# untitled.net
KiCad netlist of a schematic drawn in EAGLE
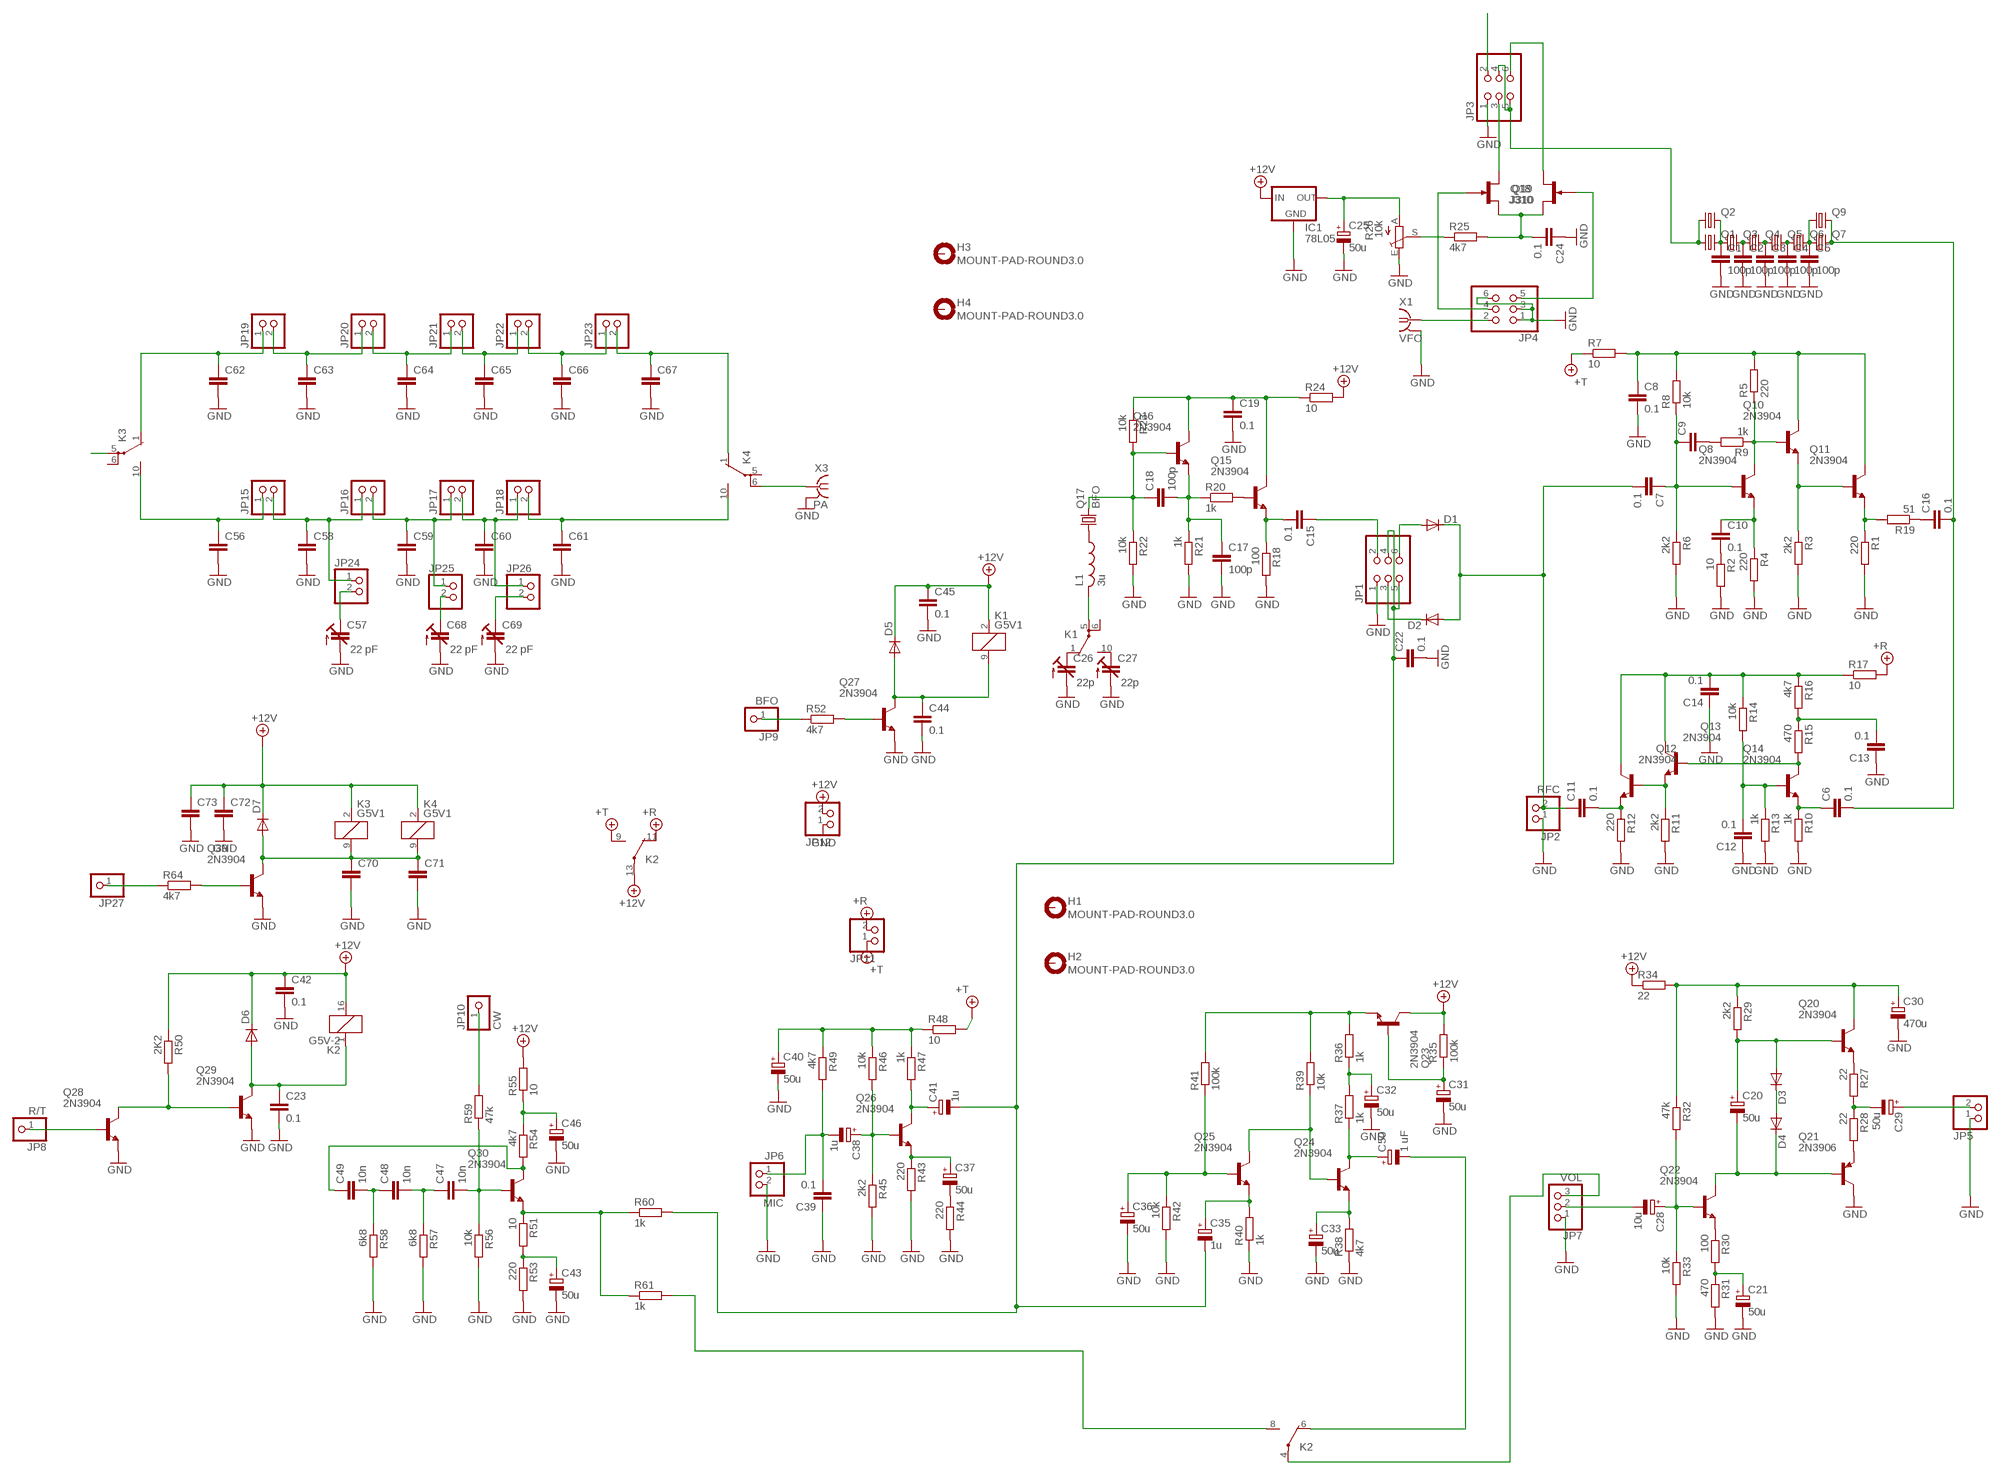
[diagram p0: schematic, sheet 1]

(export (version "E")
  (design (tool "Eeschema 10.0.6"))
  (components
    (comp (ref "C1")
      (value "100p")
      (footprint "eagle-import:C1206")
      (libsource (lib "eagle-import") (part "C-EUC1206"))
    )
    (comp (ref "C2")
      (value "100p")
      (footprint "eagle-import:C1206")
      (libsource (lib "eagle-import") (part "C-EUC1206"))
    )
    (comp (ref "C3")
      (value "100p")
      (footprint "eagle-import:C1206")
      (libsource (lib "eagle-import") (part "C-EUC1206"))
    )
    (comp (ref "C4")
      (value "100p")
      (footprint "eagle-import:C1206")
      (libsource (lib "eagle-import") (part "C-EUC1206"))
    )
    (comp (ref "C5")
      (value "100p")
      (footprint "eagle-import:C1206")
      (libsource (lib "eagle-import") (part "C-EUC1206"))
    )
    (comp (ref "C6")
      (value "0.1")
      (footprint "eagle-import:C050-024X044")
      (libsource (lib "eagle-import") (part "C-EU050-024X044"))
    )
    (comp (ref "C7")
      (value "0.1")
      (footprint "eagle-import:C050-024X044")
      (libsource (lib "eagle-import") (part "C-EU050-024X044"))
    )
    (comp (ref "C8")
      (value "0.1")
      (footprint "eagle-import:C050-024X044")
      (libsource (lib "eagle-import") (part "C-EU050-024X044"))
    )
    (comp (ref "C9")
      (value "C-EU050-024X044")
      (footprint "eagle-import:C050-024X044")
      (libsource (lib "eagle-import") (part "C-EU050-024X044"))
    )
    (comp (ref "C10")
      (value "0.1")
      (footprint "eagle-import:C050-024X044")
      (libsource (lib "eagle-import") (part "C-EU050-024X044"))
    )
    (comp (ref "C11")
      (value "0.1")
      (footprint "eagle-import:C050-024X044")
      (libsource (lib "eagle-import") (part "C-EU050-024X044"))
    )
    (comp (ref "C12")
      (value "0.1")
      (footprint "eagle-import:C050-024X044")
      (libsource (lib "eagle-import") (part "C-EU050-024X044"))
    )
    (comp (ref "C13")
      (value "0.1")
      (footprint "eagle-import:C050-024X044")
      (libsource (lib "eagle-import") (part "C-EU050-024X044"))
    )
    (comp (ref "C14")
      (value "0.1")
      (footprint "eagle-import:C050-024X044")
      (libsource (lib "eagle-import") (part "C-EU050-024X044"))
    )
    (comp (ref "C15")
      (value "0.1")
      (footprint "eagle-import:C050-024X044")
      (libsource (lib "eagle-import") (part "C-EU050-024X044"))
    )
    (comp (ref "C16")
      (value "0.1")
      (footprint "eagle-import:C050-024X044")
      (libsource (lib "eagle-import") (part "C-EU050-024X044"))
    )
    (comp (ref "C17")
      (value "100p")
      (footprint "eagle-import:C050-024X044")
      (libsource (lib "eagle-import") (part "C-EU050-024X044"))
    )
    (comp (ref "C18")
      (value "100p")
      (footprint "eagle-import:C050-024X044")
      (libsource (lib "eagle-import") (part "C-EU050-024X044"))
    )
    (comp (ref "C19")
      (value "0.1")
      (footprint "eagle-import:C050-024X044")
      (libsource (lib "eagle-import") (part "C-EU050-024X044"))
    )
    (comp (ref "C20")
      (value "50u")
      (footprint "eagle-import:E2,5-5")
      (libsource (lib "eagle-import") (part "CPOL-EUE2.5-5"))
    )
    (comp (ref "C21")
      (value "50u")
      (footprint "eagle-import:E2,5-5")
      (libsource (lib "eagle-import") (part "CPOL-EUE2.5-5"))
    )
    (comp (ref "C22")
      (value "0.1")
      (footprint "eagle-import:C050-024X044")
      (libsource (lib "eagle-import") (part "C-EU050-024X044"))
    )
    (comp (ref "C23")
      (value "0.1")
      (footprint "eagle-import:C050-024X044")
      (libsource (lib "eagle-import") (part "C-EU050-024X044"))
    )
    (comp (ref "C24")
      (value "0.1")
      (footprint "eagle-import:C050-024X044")
      (libsource (lib "eagle-import") (part "C-EU050-024X044"))
    )
    (comp (ref "C25")
      (value "50u")
      (footprint "eagle-import:E2,5-5")
      (libsource (lib "eagle-import") (part "CPOL-EUE2.5-5"))
    )
    (comp (ref "C26")
      (value "22p")
      (footprint "eagle-import:CTRIMTZ03")
      (libsource (lib "eagle-import") (part "C-TRIMMTZ03"))
    )
    (comp (ref "C27")
      (value "22p")
      (footprint "eagle-import:CTRIMTZ03")
      (libsource (lib "eagle-import") (part "C-TRIMMTZ03"))
    )
    (comp (ref "C28")
      (value "10u")
      (footprint "eagle-import:E2,5-5")
      (libsource (lib "eagle-import") (part "CPOL-EUE2.5-5"))
    )
    (comp (ref "C29")
      (value "50u")
      (footprint "eagle-import:E2,5-5")
      (libsource (lib "eagle-import") (part "CPOL-EUE2.5-5"))
    )
    (comp (ref "C30")
      (value "470u")
      (footprint "eagle-import:E2,5-5")
      (libsource (lib "eagle-import") (part "CPOL-EUE2.5-5"))
    )
    (comp (ref "C31")
      (value "50u")
      (footprint "eagle-import:E2,5-5")
      (libsource (lib "eagle-import") (part "CPOL-EUE2.5-5"))
    )
    (comp (ref "C32")
      (value "50u")
      (footprint "eagle-import:E2,5-5")
      (libsource (lib "eagle-import") (part "CPOL-EUE2.5-5"))
    )
    (comp (ref "C33")
      (value "50u")
      (footprint "eagle-import:E2,5-5")
      (libsource (lib "eagle-import") (part "CPOL-EUE2.5-5"))
    )
    (comp (ref "C35")
      (value "1u")
      (footprint "eagle-import:E2,5-5")
      (libsource (lib "eagle-import") (part "CPOL-EUE2.5-5"))
    )
    (comp (ref "C36")
      (value "50u")
      (footprint "eagle-import:E2,5-5")
      (libsource (lib "eagle-import") (part "CPOL-EUE2.5-5"))
    )
    (comp (ref "C37")
      (value "50u")
      (footprint "eagle-import:E2,5-5")
      (libsource (lib "eagle-import") (part "CPOL-EUE2.5-5"))
    )
    (comp (ref "C38")
      (value "1u")
      (footprint "eagle-import:E2,5-5")
      (libsource (lib "eagle-import") (part "CPOL-EUE2.5-5"))
    )
    (comp (ref "C39")
      (value "0.1")
      (footprint "eagle-import:C050-024X044")
      (libsource (lib "eagle-import") (part "C-EU050-024X044"))
    )
    (comp (ref "C40")
      (value "50u")
      (footprint "eagle-import:E2,5-5")
      (libsource (lib "eagle-import") (part "CPOL-EUE2.5-5"))
    )
    (comp (ref "C41")
      (value "1u")
      (footprint "eagle-import:E2,5-5")
      (libsource (lib "eagle-import") (part "CPOL-EUE2.5-5"))
    )
    (comp (ref "C42")
      (value "0.1")
      (footprint "eagle-import:C050-024X044")
      (libsource (lib "eagle-import") (part "C-EU050-024X044"))
    )
    (comp (ref "C43")
      (value "50u")
      (footprint "eagle-import:E2,5-5")
      (libsource (lib "eagle-import") (part "CPOL-EUE2.5-5"))
    )
    (comp (ref "C44")
      (value "0.1")
      (footprint "eagle-import:C050-024X044")
      (libsource (lib "eagle-import") (part "C-EU050-024X044"))
    )
    (comp (ref "C45")
      (value "0.1")
      (footprint "eagle-import:C050-024X044")
      (libsource (lib "eagle-import") (part "C-EU050-024X044"))
    )
    (comp (ref "C46")
      (value "50u")
      (footprint "eagle-import:E2,5-5")
      (libsource (lib "eagle-import") (part "CPOL-EUE2.5-5"))
    )
    (comp (ref "C47")
      (value "10n")
      (footprint "eagle-import:C050-024X044")
      (libsource (lib "eagle-import") (part "C-EU050-024X044"))
    )
    (comp (ref "C48")
      (value "10n")
      (footprint "eagle-import:C050-024X044")
      (libsource (lib "eagle-import") (part "C-EU050-024X044"))
    )
    (comp (ref "C49")
      (value "10n")
      (footprint "eagle-import:C050-024X044")
      (libsource (lib "eagle-import") (part "C-EU050-024X044"))
    )
    (comp (ref "C50")
      (value "1 uF")
      (footprint "eagle-import:E5-4")
      (libsource (lib "eagle-import") (part "CPOL-EUE5-4"))
    )
    (comp (ref "C56")
      (value "C-EU050-024X044")
      (footprint "eagle-import:C050-024X044")
      (libsource (lib "eagle-import") (part "C-EU050-024X044"))
    )
    (comp (ref "C57")
      (value "22 pF")
      (footprint "eagle-import:CTRIMTZ03")
      (libsource (lib "eagle-import") (part "C-TRIMMTZ03"))
    )
    (comp (ref "C58")
      (value "C-EU050-024X044")
      (footprint "eagle-import:C050-024X044")
      (libsource (lib "eagle-import") (part "C-EU050-024X044"))
    )
    (comp (ref "C59")
      (value "C-EU050-024X044")
      (footprint "eagle-import:C050-024X044")
      (libsource (lib "eagle-import") (part "C-EU050-024X044"))
    )
    (comp (ref "C60")
      (value "C-EU050-024X044")
      (footprint "eagle-import:C050-024X044")
      (libsource (lib "eagle-import") (part "C-EU050-024X044"))
    )
    (comp (ref "C61")
      (value "C-EU050-024X044")
      (footprint "eagle-import:C050-024X044")
      (libsource (lib "eagle-import") (part "C-EU050-024X044"))
    )
    (comp (ref "C62")
      (value "C-EU050-024X044")
      (footprint "eagle-import:C050-024X044")
      (libsource (lib "eagle-import") (part "C-EU050-024X044"))
    )
    (comp (ref "C63")
      (value "C-EU050-024X044")
      (footprint "eagle-import:C050-024X044")
      (libsource (lib "eagle-import") (part "C-EU050-024X044"))
    )
    (comp (ref "C64")
      (value "C-EU050-024X044")
      (footprint "eagle-import:C050-024X044")
      (libsource (lib "eagle-import") (part "C-EU050-024X044"))
    )
    (comp (ref "C65")
      (value "C-EU050-024X044")
      (footprint "eagle-import:C050-024X044")
      (libsource (lib "eagle-import") (part "C-EU050-024X044"))
    )
    (comp (ref "C66")
      (value "C-EU050-024X044")
      (footprint "eagle-import:C050-024X044")
      (libsource (lib "eagle-import") (part "C-EU050-024X044"))
    )
    (comp (ref "C67")
      (value "C-EU050-024X044")
      (footprint "eagle-import:C050-024X044")
      (libsource (lib "eagle-import") (part "C-EU050-024X044"))
    )
    (comp (ref "C68")
      (value "22 pF")
      (footprint "eagle-import:CTRIMTZ03")
      (libsource (lib "eagle-import") (part "C-TRIMMTZ03"))
    )
    (comp (ref "C69")
      (value "22 pF")
      (footprint "eagle-import:CTRIMTZ03")
      (libsource (lib "eagle-import") (part "C-TRIMMTZ03"))
    )
    (comp (ref "C70")
      (value "C-EU050-024X044")
      (footprint "eagle-import:C050-024X044")
      (libsource (lib "eagle-import") (part "C-EU050-024X044"))
    )
    (comp (ref "C71")
      (value "C-EU050-024X044")
      (footprint "eagle-import:C050-024X044")
      (libsource (lib "eagle-import") (part "C-EU050-024X044"))
    )
    (comp (ref "C72")
      (value "C-EU050-024X044")
      (footprint "eagle-import:C050-024X044")
      (libsource (lib "eagle-import") (part "C-EU050-024X044"))
    )
    (comp (ref "C73")
      (value "C-EU050-024X044")
      (footprint "eagle-import:C050-024X044")
      (libsource (lib "eagle-import") (part "C-EU050-024X044"))
    )
    (comp (ref "D1")
      (value "DIODE-D-5")
      (footprint "eagle-import:D-5")
      (libsource (lib "eagle-import") (part "DIODE-D-5"))
    )
    (comp (ref "D2")
      (value "DIODE-D-5")
      (footprint "eagle-import:D-5")
      (libsource (lib "eagle-import") (part "DIODE-D-5"))
    )
    (comp (ref "D3")
      (value "DIODE-D-5")
      (footprint "eagle-import:D-5")
      (libsource (lib "eagle-import") (part "DIODE-D-5"))
    )
    (comp (ref "D4")
      (value "DIODE-D-5")
      (footprint "eagle-import:D-5")
      (libsource (lib "eagle-import") (part "DIODE-D-5"))
    )
    (comp (ref "D5")
      (value "DIODE-D-5")
      (footprint "eagle-import:D-5")
      (libsource (lib "eagle-import") (part "DIODE-D-5"))
    )
    (comp (ref "D6")
      (value "DIODE-D-5")
      (footprint "eagle-import:D-5")
      (libsource (lib "eagle-import") (part "DIODE-D-5"))
    )
    (comp (ref "D7")
      (value "DIODE-D-5")
      (footprint "eagle-import:D-5")
      (libsource (lib "eagle-import") (part "DIODE-D-5"))
    )
    (comp (ref "H1")
      (value "MOUNT-PAD-ROUND3.0")
      (footprint "eagle-import:3,0-PAD")
      (libsource (lib "eagle-import") (part "MOUNT-PAD-ROUND3.0"))
    )
    (comp (ref "H2")
      (value "MOUNT-PAD-ROUND3.0")
      (footprint "eagle-import:3,0-PAD")
      (libsource (lib "eagle-import") (part "MOUNT-PAD-ROUND3.0"))
    )
    (comp (ref "H3")
      (value "MOUNT-PAD-ROUND3.0")
      (footprint "eagle-import:3,0-PAD")
      (libsource (lib "eagle-import") (part "MOUNT-PAD-ROUND3.0"))
    )
    (comp (ref "H4")
      (value "MOUNT-PAD-ROUND3.0")
      (footprint "eagle-import:3,0-PAD")
      (libsource (lib "eagle-import") (part "MOUNT-PAD-ROUND3.0"))
    )
    (comp (ref "IC1")
      (value "78L05")
      (footprint "eagle-import:78LXX")
      (libsource (lib "eagle-import") (part "78LXX"))
    )
    (comp (ref "JP1")
      (value "PINHD-2X3")
      (footprint "eagle-import:2X03")
      (libsource (lib "eagle-import") (part "PINHD-2X3"))
    )
    (comp (ref "JP2")
      (value "RFC")
      (footprint "eagle-import:1X02")
      (libsource (lib "eagle-import") (part "PINHD-1X2"))
    )
    (comp (ref "JP3")
      (value "PINHD-2X3")
      (footprint "eagle-import:2X03")
      (libsource (lib "eagle-import") (part "PINHD-2X3"))
    )
    (comp (ref "JP4")
      (value "PINHD-2X3")
      (footprint "eagle-import:2X03")
      (libsource (lib "eagle-import") (part "PINHD-2X3"))
    )
    (comp (ref "JP5")
      (value "PINHD-1X2")
      (footprint "eagle-import:1X02")
      (libsource (lib "eagle-import") (part "PINHD-1X2"))
    )
    (comp (ref "JP6")
      (value "MIC")
      (footprint "eagle-import:1X02")
      (libsource (lib "eagle-import") (part "PINHD-1X2"))
    )
    (comp (ref "JP7")
      (value "VOL")
      (footprint "eagle-import:1X03")
      (libsource (lib "eagle-import") (part "PINHD-1X3"))
    )
    (comp (ref "JP8")
      (value "R/T")
      (footprint "eagle-import:1X01")
      (libsource (lib "eagle-import") (part "PINHD-1X1"))
    )
    (comp (ref "JP9")
      (value "BFO")
      (footprint "eagle-import:1X01")
      (libsource (lib "eagle-import") (part "PINHD-1X1"))
    )
    (comp (ref "JP10")
      (value "CW")
      (footprint "eagle-import:1X01")
      (libsource (lib "eagle-import") (part "PINHD-1X1"))
    )
    (comp (ref "JP11")
      (value "PINHD-1X2")
      (footprint "eagle-import:1X02")
      (libsource (lib "eagle-import") (part "PINHD-1X2"))
    )
    (comp (ref "JP12")
      (value "PINHD-1X2")
      (footprint "eagle-import:1X02")
      (libsource (lib "eagle-import") (part "PINHD-1X2"))
    )
    (comp (ref "JP15")
      (value "PINHD-1X2")
      (footprint "eagle-import:1X02")
      (libsource (lib "eagle-import") (part "PINHD-1X2"))
    )
    (comp (ref "JP16")
      (value "PINHD-1X2")
      (footprint "eagle-import:1X02")
      (libsource (lib "eagle-import") (part "PINHD-1X2"))
    )
    (comp (ref "JP17")
      (value "PINHD-1X2")
      (footprint "eagle-import:1X02")
      (libsource (lib "eagle-import") (part "PINHD-1X2"))
    )
    (comp (ref "JP18")
      (value "PINHD-1X2")
      (footprint "eagle-import:1X02")
      (libsource (lib "eagle-import") (part "PINHD-1X2"))
    )
    (comp (ref "JP19")
      (value "PINHD-1X2")
      (footprint "eagle-import:1X02")
      (libsource (lib "eagle-import") (part "PINHD-1X2"))
    )
    (comp (ref "JP20")
      (value "PINHD-1X2")
      (footprint "eagle-import:1X02")
      (libsource (lib "eagle-import") (part "PINHD-1X2"))
    )
    (comp (ref "JP21")
      (value "PINHD-1X2")
      (footprint "eagle-import:1X02")
      (libsource (lib "eagle-import") (part "PINHD-1X2"))
    )
    (comp (ref "JP22")
      (value "PINHD-1X2")
      (footprint "eagle-import:1X02")
      (libsource (lib "eagle-import") (part "PINHD-1X2"))
    )
    (comp (ref "JP23")
      (value "PINHD-1X2")
      (footprint "eagle-import:1X02")
      (libsource (lib "eagle-import") (part "PINHD-1X2"))
    )
    (comp (ref "JP24")
      (value "PINHD-1X2")
      (footprint "eagle-import:1X02")
      (libsource (lib "eagle-import") (part "PINHD-1X2"))
    )
    (comp (ref "JP25")
      (value "PINHD-1X2")
      (footprint "eagle-import:1X02")
      (libsource (lib "eagle-import") (part "PINHD-1X2"))
    )
    (comp (ref "JP26")
      (value "PINHD-1X2")
      (footprint "eagle-import:1X02")
      (libsource (lib "eagle-import") (part "PINHD-1X2"))
    )
    (comp (ref "JP27")
      (value "PINHD-1X1")
      (footprint "eagle-import:1X01")
      (libsource (lib "eagle-import") (part "PINHD-1X1"))
    )
    (comp (ref "K1")
      (value "G5V1")
      (footprint "eagle-import:G5V1")
      (fields (field (name "MPN") "G5V-1-DC24"))
      (libsource (lib "eagle-import") (part "G5V1"))
    )
    (comp (ref "K2")
      (value "G5V-2")
      (footprint "eagle-import:G5V-2")
      (fields (field (name "MPN") "G5V-2 5DC"))
      (libsource (lib "eagle-import") (part "G5V-2"))
    )
    (comp (ref "K3")
      (value "G5V1")
      (footprint "eagle-import:G5V1")
      (fields (field (name "MPN") "G5V-1-DC24"))
      (libsource (lib "eagle-import") (part "G5V1"))
    )
    (comp (ref "K4")
      (value "G5V1")
      (footprint "eagle-import:G5V1")
      (fields (field (name "MPN") "G5V-1-DC24"))
      (libsource (lib "eagle-import") (part "G5V1"))
    )
    (comp (ref "L1")
      (value "3u")
      (footprint "eagle-import:0207_2V")
      (libsource (lib "eagle-import") (part "L-US0207/2V"))
    )
    (comp (ref "Q1")
      (value "CRYSTALHC49S")
      (footprint "eagle-import:HC49_S")
      (libsource (lib "eagle-import") (part "CRYSTALHC49S"))
    )
    (comp (ref "Q2")
      (value "CRYSTALHC49S")
      (footprint "eagle-import:HC49_S")
      (libsource (lib "eagle-import") (part "CRYSTALHC49S"))
    )
    (comp (ref "Q3")
      (value "CRYSTALHC49S")
      (footprint "eagle-import:HC49_S")
      (libsource (lib "eagle-import") (part "CRYSTALHC49S"))
    )
    (comp (ref "Q4")
      (value "CRYSTALHC49S")
      (footprint "eagle-import:HC49_S")
      (libsource (lib "eagle-import") (part "CRYSTALHC49S"))
    )
    (comp (ref "Q5")
      (value "CRYSTALHC49S")
      (footprint "eagle-import:HC49_S")
      (libsource (lib "eagle-import") (part "CRYSTALHC49S"))
    )
    (comp (ref "Q6")
      (value "CRYSTALHC49S")
      (footprint "eagle-import:HC49_S")
      (libsource (lib "eagle-import") (part "CRYSTALHC49S"))
    )
    (comp (ref "Q7")
      (value "CRYSTALHC49S")
      (footprint "eagle-import:HC49_S")
      (libsource (lib "eagle-import") (part "CRYSTALHC49S"))
    )
    (comp (ref "Q8")
      (value "2N3904")
      (footprint "eagle-import:TO92")
      (libsource (lib "eagle-import") (part "2N3904"))
    )
    (comp (ref "Q9")
      (value "CRYSTALHC49S")
      (footprint "eagle-import:HC49_S")
      (libsource (lib "eagle-import") (part "CRYSTALHC49S"))
    )
    (comp (ref "Q10")
      (value "2N3904")
      (footprint "eagle-import:TO92")
      (libsource (lib "eagle-import") (part "2N3904"))
    )
    (comp (ref "Q11")
      (value "2N3904")
      (footprint "eagle-import:TO92")
      (libsource (lib "eagle-import") (part "2N3904"))
    )
    (comp (ref "Q12")
      (value "2N3904")
      (footprint "eagle-import:TO92")
      (libsource (lib "eagle-import") (part "2N3904"))
    )
    (comp (ref "Q13")
      (value "2N3904")
      (footprint "eagle-import:TO92")
      (libsource (lib "eagle-import") (part "2N3904"))
    )
    (comp (ref "Q14")
      (value "2N3904")
      (footprint "eagle-import:TO92")
      (libsource (lib "eagle-import") (part "2N3904"))
    )
    (comp (ref "Q15")
      (value "2N3904")
      (footprint "eagle-import:TO92")
      (libsource (lib "eagle-import") (part "2N3904"))
    )
    (comp (ref "Q16")
      (value "2N3904")
      (footprint "eagle-import:TO92")
      (libsource (lib "eagle-import") (part "2N3904"))
    )
    (comp (ref "Q17")
      (value "BFO")
      (footprint "eagle-import:HC49_S")
      (fields (field (name "OC_FARNELL") "1667008") (field (name "OC_NEWARK") "unknown"))
      (libsource (lib "eagle-import") (part "CRYSTALHC49S"))
    )
    (comp (ref "Q18")
      (value "J310")
      (footprint "eagle-import:TO92R")
      (libsource (lib "eagle-import") (part "J310"))
    )
    (comp (ref "Q19")
      (value "J310")
      (footprint "eagle-import:TO92R")
      (libsource (lib "eagle-import") (part "J310"))
    )
    (comp (ref "Q20")
      (value "2N3904")
      (footprint "eagle-import:TO92")
      (libsource (lib "eagle-import") (part "2N3904"))
    )
    (comp (ref "Q21")
      (value "2N3906")
      (footprint "eagle-import:TO92")
      (libsource (lib "eagle-import") (part "2N3906"))
    )
    (comp (ref "Q22")
      (value "2N3904")
      (footprint "eagle-import:TO92")
      (libsource (lib "eagle-import") (part "2N3904"))
    )
    (comp (ref "Q23")
      (value "2N3904")
      (footprint "eagle-import:TO92")
      (libsource (lib "eagle-import") (part "2N3904"))
    )
    (comp (ref "Q24")
      (value "2N3904")
      (footprint "eagle-import:TO92")
      (libsource (lib "eagle-import") (part "2N3904"))
    )
    (comp (ref "Q25")
      (value "2N3904")
      (footprint "eagle-import:TO92")
      (libsource (lib "eagle-import") (part "2N3904"))
    )
    (comp (ref "Q26")
      (value "2N3904")
      (footprint "eagle-import:TO92")
      (libsource (lib "eagle-import") (part "2N3904"))
    )
    (comp (ref "Q27")
      (value "2N3904")
      (footprint "eagle-import:TO92")
      (libsource (lib "eagle-import") (part "2N3904"))
    )
    (comp (ref "Q28")
      (value "2N3904")
      (footprint "eagle-import:TO92")
      (libsource (lib "eagle-import") (part "2N3904"))
    )
    (comp (ref "Q29")
      (value "2N3904")
      (footprint "eagle-import:TO92")
      (libsource (lib "eagle-import") (part "2N3904"))
    )
    (comp (ref "Q30")
      (value "2N3904")
      (footprint "eagle-import:TO92")
      (libsource (lib "eagle-import") (part "2N3904"))
    )
    (comp (ref "Q39")
      (value "2N3904")
      (footprint "eagle-import:TO92")
      (libsource (lib "eagle-import") (part "2N3904"))
    )
    (comp (ref "R1")
      (value "220")
      (footprint "eagle-import:0204_5")
      (libsource (lib "eagle-import") (part "R-EU_0204/5"))
    )
    (comp (ref "R2")
      (value "10")
      (footprint "eagle-import:0204_5")
      (libsource (lib "eagle-import") (part "R-EU_0204/5"))
    )
    (comp (ref "R3")
      (value "2k2")
      (footprint "eagle-import:0204_5")
      (libsource (lib "eagle-import") (part "R-EU_0204/5"))
    )
    (comp (ref "R4")
      (value "220")
      (footprint "eagle-import:0204_5")
      (libsource (lib "eagle-import") (part "R-EU_0204/5"))
    )
    (comp (ref "R5")
      (value "220")
      (footprint "eagle-import:0204_5")
      (libsource (lib "eagle-import") (part "R-EU_0204/5"))
    )
    (comp (ref "R6")
      (value "2k2")
      (footprint "eagle-import:0204_5")
      (libsource (lib "eagle-import") (part "R-EU_0204/5"))
    )
    (comp (ref "R7")
      (value "10")
      (footprint "eagle-import:0204_5")
      (libsource (lib "eagle-import") (part "R-EU_0204/5"))
    )
    (comp (ref "R8")
      (value "10k")
      (footprint "eagle-import:0204_5")
      (libsource (lib "eagle-import") (part "R-EU_0204/5"))
    )
    (comp (ref "R9")
      (value "1k")
      (footprint "eagle-import:0204_5")
      (libsource (lib "eagle-import") (part "R-EU_0204/5"))
    )
    (comp (ref "R10")
      (value "1k")
      (footprint "eagle-import:0204_5")
      (libsource (lib "eagle-import") (part "R-EU_0204/5"))
    )
    (comp (ref "R11")
      (value "2k2")
      (footprint "eagle-import:0204_5")
      (libsource (lib "eagle-import") (part "R-EU_0204/5"))
    )
    (comp (ref "R12")
      (value "220")
      (footprint "eagle-import:0204_5")
      (libsource (lib "eagle-import") (part "R-EU_0204/5"))
    )
    (comp (ref "R13")
      (value "1k")
      (footprint "eagle-import:0204_5")
      (libsource (lib "eagle-import") (part "R-EU_0204/5"))
    )
    (comp (ref "R14")
      (value "10k")
      (footprint "eagle-import:0204_5")
      (libsource (lib "eagle-import") (part "R-EU_0204/5"))
    )
    (comp (ref "R15")
      (value "470")
      (footprint "eagle-import:0204_5")
      (libsource (lib "eagle-import") (part "R-EU_0204/5"))
    )
    (comp (ref "R16")
      (value "4k7")
      (footprint "eagle-import:0204_5")
      (libsource (lib "eagle-import") (part "R-EU_0204/5"))
    )
    (comp (ref "R17")
      (value "10")
      (footprint "eagle-import:0204_5")
      (libsource (lib "eagle-import") (part "R-EU_0204/5"))
    )
    (comp (ref "R18")
      (value "100")
      (footprint "eagle-import:0204_5")
      (libsource (lib "eagle-import") (part "R-EU_0204/5"))
    )
    (comp (ref "R19")
      (value "51")
      (footprint "eagle-import:0204_5")
      (libsource (lib "eagle-import") (part "R-EU_0204/5"))
    )
    (comp (ref "R20")
      (value "1k")
      (footprint "eagle-import:0204_5")
      (libsource (lib "eagle-import") (part "R-EU_0204/5"))
    )
    (comp (ref "R21")
      (value "1k")
      (footprint "eagle-import:0204_5")
      (libsource (lib "eagle-import") (part "R-EU_0204/5"))
    )
    (comp (ref "R22")
      (value "10k")
      (footprint "eagle-import:0204_5")
      (libsource (lib "eagle-import") (part "R-EU_0204/5"))
    )
    (comp (ref "R23")
      (value "10k")
      (footprint "eagle-import:0204_5")
      (libsource (lib "eagle-import") (part "R-EU_0204/5"))
    )
    (comp (ref "R24")
      (value "10")
      (footprint "eagle-import:0204_5")
      (libsource (lib "eagle-import") (part "R-EU_0204/5"))
    )
    (comp (ref "R25")
      (value "4k7")
      (footprint "eagle-import:0204_5")
      (libsource (lib "eagle-import") (part "R-EU_0204/5"))
    )
    (comp (ref "R26")
      (value "10k")
      (footprint "eagle-import:CA6V")
      (libsource (lib "eagle-import") (part "TRIM_EU-CA6V"))
    )
    (comp (ref "R27")
      (value "22")
      (footprint "eagle-import:0204_5")
      (libsource (lib "eagle-import") (part "R-EU_0204/5"))
    )
    (comp (ref "R28")
      (value "22")
      (footprint "eagle-import:0204_5")
      (libsource (lib "eagle-import") (part "R-EU_0204/5"))
    )
    (comp (ref "R29")
      (value "2k2")
      (footprint "eagle-import:0204_5")
      (libsource (lib "eagle-import") (part "R-EU_0204/5"))
    )
    (comp (ref "R30")
      (value "100")
      (footprint "eagle-import:0204_5")
      (libsource (lib "eagle-import") (part "R-EU_0204/5"))
    )
    (comp (ref "R31")
      (value "470")
      (footprint "eagle-import:0204_5")
      (libsource (lib "eagle-import") (part "R-EU_0204/5"))
    )
    (comp (ref "R32")
      (value "47k")
      (footprint "eagle-import:0204_5")
      (libsource (lib "eagle-import") (part "R-EU_0204/5"))
    )
    (comp (ref "R33")
      (value "10k")
      (footprint "eagle-import:0204_5")
      (libsource (lib "eagle-import") (part "R-EU_0204/5"))
    )
    (comp (ref "R34")
      (value "22")
      (footprint "eagle-import:0204_5")
      (libsource (lib "eagle-import") (part "R-EU_0204/5"))
    )
    (comp (ref "R35")
      (value "100k")
      (footprint "eagle-import:0204_5")
      (libsource (lib "eagle-import") (part "R-EU_0204/5"))
    )
    (comp (ref "R36")
      (value "1k")
      (footprint "eagle-import:0204_5")
      (libsource (lib "eagle-import") (part "R-EU_0204/5"))
    )
    (comp (ref "R37")
      (value "1k")
      (footprint "eagle-import:0204_5")
      (libsource (lib "eagle-import") (part "R-EU_0204/5"))
    )
    (comp (ref "R38")
      (value "4k7")
      (footprint "eagle-import:0204_5")
      (libsource (lib "eagle-import") (part "R-EU_0204/5"))
    )
    (comp (ref "R39")
      (value "10k")
      (footprint "eagle-import:0204_5")
      (libsource (lib "eagle-import") (part "R-EU_0204/5"))
    )
    (comp (ref "R40")
      (value "1k")
      (footprint "eagle-import:0204_5")
      (libsource (lib "eagle-import") (part "R-EU_0204/5"))
    )
    (comp (ref "R41")
      (value "100k")
      (footprint "eagle-import:0204_5")
      (libsource (lib "eagle-import") (part "R-EU_0204/5"))
    )
    (comp (ref "R42")
      (value "10k")
      (footprint "eagle-import:0204_5")
      (libsource (lib "eagle-import") (part "R-EU_0204/5"))
    )
    (comp (ref "R43")
      (value "220")
      (footprint "eagle-import:0204_5")
      (libsource (lib "eagle-import") (part "R-EU_0204/5"))
    )
    (comp (ref "R44")
      (value "220")
      (footprint "eagle-import:0204_5")
      (libsource (lib "eagle-import") (part "R-EU_0204/5"))
    )
    (comp (ref "R45")
      (value "2k2")
      (footprint "eagle-import:0204_5")
      (libsource (lib "eagle-import") (part "R-EU_0204/5"))
    )
    (comp (ref "R46")
      (value "10k")
      (footprint "eagle-import:0204_5")
      (libsource (lib "eagle-import") (part "R-EU_0204/5"))
    )
    (comp (ref "R47")
      (value "1k")
      (footprint "eagle-import:0204_5")
      (libsource (lib "eagle-import") (part "R-EU_0204/5"))
    )
    (comp (ref "R48")
      (value "10")
      (footprint "eagle-import:0204_5")
      (libsource (lib "eagle-import") (part "R-EU_0204/5"))
    )
    (comp (ref "R49")
      (value "4k7")
      (footprint "eagle-import:0204_5")
      (libsource (lib "eagle-import") (part "R-EU_0204/5"))
    )
    (comp (ref "R50")
      (value "2K2")
      (footprint "eagle-import:0204_5")
      (libsource (lib "eagle-import") (part "R-EU_0204/5"))
    )
    (comp (ref "R51")
      (value "10")
      (footprint "eagle-import:0204_5")
      (libsource (lib "eagle-import") (part "R-EU_0204/5"))
    )
    (comp (ref "R52")
      (value "4k7")
      (footprint "eagle-import:0204_5")
      (libsource (lib "eagle-import") (part "R-EU_0204/5"))
    )
    (comp (ref "R53")
      (value "220")
      (footprint "eagle-import:0204_5")
      (libsource (lib "eagle-import") (part "R-EU_0204/5"))
    )
    (comp (ref "R54")
      (value "4k7")
      (footprint "eagle-import:0204_5")
      (libsource (lib "eagle-import") (part "R-EU_0204/5"))
    )
    (comp (ref "R55")
      (value "10")
      (footprint "eagle-import:0204_5")
      (libsource (lib "eagle-import") (part "R-EU_0204/5"))
    )
    (comp (ref "R56")
      (value "10k")
      (footprint "eagle-import:0204_5")
      (libsource (lib "eagle-import") (part "R-EU_0204/5"))
    )
    (comp (ref "R57")
      (value "6k8")
      (footprint "eagle-import:0204_5")
      (libsource (lib "eagle-import") (part "R-EU_0204/5"))
    )
    (comp (ref "R58")
      (value "6k8")
      (footprint "eagle-import:0204_5")
      (libsource (lib "eagle-import") (part "R-EU_0204/5"))
    )
    (comp (ref "R59")
      (value "47k")
      (footprint "eagle-import:0204_5")
      (libsource (lib "eagle-import") (part "R-EU_0204/5"))
    )
    (comp (ref "R60")
      (value "1k")
      (footprint "eagle-import:0204_5")
      (libsource (lib "eagle-import") (part "R-EU_0204/5"))
    )
    (comp (ref "R61")
      (value "1k")
      (footprint "eagle-import:0204_5")
      (libsource (lib "eagle-import") (part "R-EU_0204/5"))
    )
    (comp (ref "R64")
      (value "4k7")
      (footprint "eagle-import:0204_5")
      (libsource (lib "eagle-import") (part "R-EU_0204/5"))
    )
    (comp (ref "X1")
      (value "VFO")
      (footprint "eagle-import:BU-SMA-V")
      (libsource (lib "eagle-import") (part "BU-SMA-V"))
    )
    (comp (ref "X3")
      (value "PA")
      (footprint "eagle-import:BU-SMA-V")
      (fields (field (name "OC_FARNELL") "unknown") (field (name "OC_NEWARK") "unknown"))
      (libsource (lib "eagle-import") (part "BU-SMA-V"))
    )
  )
  (nets
    (net (code "1") (name "+12V") (class "Default")
      (node (ref "C42") (pin "1") (pinfunction "1_1") (pintype "passive"))
      (node (ref "C45") (pin "1") (pinfunction "1_1") (pintype "passive"))
      (node (ref "C72") (pin "1") (pinfunction "1_1") (pintype "passive"))
      (node (ref "C73") (pin "1") (pinfunction "1_1") (pintype "passive"))
      (node (ref "D5") (pin "C") (pinfunction "C_C") (pintype "passive"))
      (node (ref "D6") (pin "C") (pinfunction "C_C") (pintype "passive"))
      (node (ref "D7") (pin "C") (pinfunction "C_C") (pintype "passive"))
      (node (ref "IC1") (pin "IN") (pinfunction "IN_IN") (pintype "input"))
      (node (ref "JP12") (pin "2") (pinfunction "2_2") (pintype "passive"))
      (node (ref "K1") (pin "2") (pinfunction "1_2") (pintype "passive"))
      (node (ref "K2") (pin "13") (pinfunction "P_13") (pintype "passive"))
      (node (ref "K2") (pin "16") (pinfunction "2_16") (pintype "passive"))
      (node (ref "K3") (pin "2") (pinfunction "1_2") (pintype "passive"))
      (node (ref "K4") (pin "2") (pinfunction "1_2") (pintype "passive"))
      (node (ref "Q23") (pin "1") (pinfunction "C_1") (pintype "passive"))
      (node (ref "R24") (pin "2") (pinfunction "2_2") (pintype "passive"))
      (node (ref "R34") (pin "1") (pinfunction "1_1") (pintype "passive"))
      (node (ref "R35") (pin "2") (pinfunction "2_2") (pintype "passive"))
      (node (ref "R50") (pin "1") (pinfunction "1_1") (pintype "passive"))
      (node (ref "R55") (pin "2") (pinfunction "2_2") (pintype "passive"))
    )
    (net (code "2") (name "+R") (class "Default")
      (node (ref "JP11") (pin "2") (pinfunction "2_2") (pintype "passive"))
      (node (ref "K2") (pin "11") (pinfunction "O_11") (pintype "passive"))
      (node (ref "R17") (pin "2") (pinfunction "2_2") (pintype "passive"))
    )
    (net (code "3") (name "+T") (class "Default")
      (node (ref "JP11") (pin "1") (pinfunction "1_1") (pintype "passive"))
      (node (ref "K2") (pin "9") (pinfunction "S_9") (pintype "passive"))
      (node (ref "R48") (pin "2") (pinfunction "2_2") (pintype "passive"))
      (node (ref "R7") (pin "1") (pinfunction "1_1") (pintype "passive"))
    )
    (net (code "4") (name "/N$116") (class "Default")
      (node (ref "JP3") (pin "2") (pinfunction "2_2") (pintype "passive"))
      (node (ref "K3") (pin "5") (pinfunction "P_5") (pintype "passive"))
    )
    (net (code "5") (name "GND") (class "Default")
      (node (ref "C1") (pin "2") (pinfunction "2_2") (pintype "passive"))
      (node (ref "C12") (pin "1") (pinfunction "1_1") (pintype "passive"))
      (node (ref "C13") (pin "1") (pinfunction "1_1") (pintype "passive"))
      (node (ref "C14") (pin "1") (pinfunction "1_1") (pintype "passive"))
      (node (ref "C17") (pin "2") (pinfunction "2_2") (pintype "passive"))
      (node (ref "C19") (pin "2") (pinfunction "2_2") (pintype "passive"))
      (node (ref "C2") (pin "2") (pinfunction "2_2") (pintype "passive"))
      (node (ref "C21") (pin "-") (pinfunction "-_-") (pintype "passive"))
      (node (ref "C22") (pin "2") (pinfunction "2_2") (pintype "passive"))
      (node (ref "C23") (pin "2") (pinfunction "2_2") (pintype "passive"))
      (node (ref "C24") (pin "1") (pinfunction "1_1") (pintype "passive"))
      (node (ref "C25") (pin "-") (pinfunction "-_-") (pintype "passive"))
      (node (ref "C26") (pin "2") (pinfunction "A_2") (pintype "passive"))
      (node (ref "C27") (pin "2") (pinfunction "A_2") (pintype "passive"))
      (node (ref "C3") (pin "2") (pinfunction "2_2") (pintype "passive"))
      (node (ref "C30") (pin "-") (pinfunction "-_-") (pintype "passive"))
      (node (ref "C31") (pin "-") (pinfunction "-_-") (pintype "passive"))
      (node (ref "C32") (pin "-") (pinfunction "-_-") (pintype "passive"))
      (node (ref "C33") (pin "-") (pinfunction "-_-") (pintype "passive"))
      (node (ref "C36") (pin "-") (pinfunction "-_-") (pintype "passive"))
      (node (ref "C39") (pin "1") (pinfunction "1_1") (pintype "passive"))
      (node (ref "C4") (pin "2") (pinfunction "2_2") (pintype "passive"))
      (node (ref "C40") (pin "-") (pinfunction "-_-") (pintype "passive"))
      (node (ref "C42") (pin "2") (pinfunction "2_2") (pintype "passive"))
      (node (ref "C43") (pin "-") (pinfunction "-_-") (pintype "passive"))
      (node (ref "C44") (pin "2") (pinfunction "2_2") (pintype "passive"))
      (node (ref "C45") (pin "2") (pinfunction "2_2") (pintype "passive"))
      (node (ref "C46") (pin "-") (pinfunction "-_-") (pintype "passive"))
      (node (ref "C5") (pin "2") (pinfunction "2_2") (pintype "passive"))
      (node (ref "C56") (pin "2") (pinfunction "2_2") (pintype "passive"))
      (node (ref "C57") (pin "2") (pinfunction "A_2") (pintype "passive"))
      (node (ref "C58") (pin "2") (pinfunction "2_2") (pintype "passive"))
      (node (ref "C59") (pin "2") (pinfunction "2_2") (pintype "passive"))
      (node (ref "C60") (pin "2") (pinfunction "2_2") (pintype "passive"))
      (node (ref "C61") (pin "2") (pinfunction "2_2") (pintype "passive"))
      (node (ref "C62") (pin "2") (pinfunction "2_2") (pintype "passive"))
      (node (ref "C63") (pin "2") (pinfunction "2_2") (pintype "passive"))
      (node (ref "C64") (pin "2") (pinfunction "2_2") (pintype "passive"))
      (node (ref "C65") (pin "2") (pinfunction "2_2") (pintype "passive"))
      (node (ref "C66") (pin "2") (pinfunction "2_2") (pintype "passive"))
      (node (ref "C67") (pin "2") (pinfunction "2_2") (pintype "passive"))
      (node (ref "C68") (pin "2") (pinfunction "A_2") (pintype "passive"))
      (node (ref "C69") (pin "2") (pinfunction "A_2") (pintype "passive"))
      (node (ref "C70") (pin "2") (pinfunction "2_2") (pintype "passive"))
      (node (ref "C71") (pin "2") (pinfunction "2_2") (pintype "passive"))
      (node (ref "C72") (pin "2") (pinfunction "2_2") (pintype "passive"))
      (node (ref "C73") (pin "2") (pinfunction "2_2") (pintype "passive"))
      (node (ref "C8") (pin "2") (pinfunction "2_2") (pintype "passive"))
      (node (ref "IC1") (pin "GND") (pinfunction "GND_GND") (pintype "input"))
      (node (ref "JP1") (pin "1") (pinfunction "1_1") (pintype "passive"))
      (node (ref "JP12") (pin "1") (pinfunction "1_1") (pintype "passive"))
      (node (ref "JP2") (pin "1") (pinfunction "1_1") (pintype "passive"))
      (node (ref "JP3") (pin "1") (pinfunction "1_1") (pintype "passive"))
      (node (ref "JP4") (pin "1") (pinfunction "1_1") (pintype "passive"))
      (node (ref "JP4") (pin "3") (pinfunction "3_3") (pintype "passive"))
      (node (ref "JP4") (pin "6") (pinfunction "6_6") (pintype "passive"))
      (node (ref "JP5") (pin "1") (pinfunction "1_1") (pintype "passive"))
      (node (ref "JP6") (pin "2") (pinfunction "2_2") (pintype "passive"))
      (node (ref "JP7") (pin "1") (pinfunction "1_1") (pintype "passive"))
      (node (ref "Q21") (pin "1") (pinfunction "C_1") (pintype "passive"))
      (node (ref "Q27") (pin "3") (pinfunction "E_3") (pintype "passive"))
      (node (ref "Q28") (pin "3") (pinfunction "E_3") (pintype "passive"))
      (node (ref "Q29") (pin "3") (pinfunction "E_3") (pintype "passive"))
      (node (ref "Q39") (pin "3") (pinfunction "E_3") (pintype "passive"))
      (node (ref "R1") (pin "2") (pinfunction "2_2") (pintype "passive"))
      (node (ref "R10") (pin "2") (pinfunction "2_2") (pintype "passive"))
      (node (ref "R11") (pin "2") (pinfunction "2_2") (pintype "passive"))
      (node (ref "R12") (pin "2") (pinfunction "2_2") (pintype "passive"))
      (node (ref "R13") (pin "2") (pinfunction "2_2") (pintype "passive"))
      (node (ref "R18") (pin "2") (pinfunction "2_2") (pintype "passive"))
      (node (ref "R2") (pin "2") (pinfunction "2_2") (pintype "passive"))
      (node (ref "R21") (pin "2") (pinfunction "2_2") (pintype "passive"))
      (node (ref "R22") (pin "2") (pinfunction "2_2") (pintype "passive"))
      (node (ref "R26") (pin "E") (pinfunction "E_E") (pintype "passive"))
      (node (ref "R3") (pin "2") (pinfunction "2_2") (pintype "passive"))
      (node (ref "R31") (pin "2") (pinfunction "2_2") (pintype "passive"))
      (node (ref "R33") (pin "2") (pinfunction "2_2") (pintype "passive"))
      (node (ref "R38") (pin "1") (pinfunction "1_1") (pintype "passive"))
      (node (ref "R4") (pin "2") (pinfunction "2_2") (pintype "passive"))
      (node (ref "R40") (pin "1") (pinfunction "1_1") (pintype "passive"))
      (node (ref "R42") (pin "2") (pinfunction "2_2") (pintype "passive"))
      (node (ref "R43") (pin "2") (pinfunction "2_2") (pintype "passive"))
      (node (ref "R44") (pin "2") (pinfunction "2_2") (pintype "passive"))
      (node (ref "R45") (pin "2") (pinfunction "2_2") (pintype "passive"))
      (node (ref "R53") (pin "2") (pinfunction "2_2") (pintype "passive"))
      (node (ref "R56") (pin "2") (pinfunction "2_2") (pintype "passive"))
      (node (ref "R57") (pin "2") (pinfunction "2_2") (pintype "passive"))
      (node (ref "R58") (pin "2") (pinfunction "2_2") (pintype "passive"))
      (node (ref "R6") (pin "2") (pinfunction "2_2") (pintype "passive"))
      (node (ref "X1") (pin "2") (pinfunction "GND_2") (pintype "power_in"))
      (node (ref "X3") (pin "2") (pinfunction "GND_2") (pintype "power_in"))
    )
    (net (code "6") (name "Net-(C1-Pad1)") (class "Default")
      (node (ref "C1") (pin "1") (pinfunction "1_1") (pintype "passive"))
      (node (ref "Q1") (pin "2") (pinfunction "2_2") (pintype "passive"))
      (node (ref "Q2") (pin "2") (pinfunction "2_2") (pintype "passive"))
      (node (ref "Q3") (pin "1") (pinfunction "1_1") (pintype "passive"))
    )
    (net (code "7") (name "Net-(C2-Pad1)") (class "Default")
      (node (ref "C2") (pin "1") (pinfunction "1_1") (pintype "passive"))
      (node (ref "Q3") (pin "2") (pinfunction "2_2") (pintype "passive"))
      (node (ref "Q4") (pin "1") (pinfunction "1_1") (pintype "passive"))
    )
    (net (code "8") (name "Net-(C3-Pad1)") (class "Default")
      (node (ref "C3") (pin "1") (pinfunction "1_1") (pintype "passive"))
      (node (ref "Q4") (pin "2") (pinfunction "2_2") (pintype "passive"))
      (node (ref "Q5") (pin "1") (pinfunction "1_1") (pintype "passive"))
    )
    (net (code "9") (name "Net-(C4-Pad1)") (class "Default")
      (node (ref "C4") (pin "1") (pinfunction "1_1") (pintype "passive"))
      (node (ref "Q5") (pin "2") (pinfunction "2_2") (pintype "passive"))
      (node (ref "Q6") (pin "1") (pinfunction "1_1") (pintype "passive"))
    )
    (net (code "10") (name "Net-(C5-Pad1)") (class "Default")
      (node (ref "C5") (pin "1") (pinfunction "1_1") (pintype "passive"))
      (node (ref "Q6") (pin "2") (pinfunction "2_2") (pintype "passive"))
      (node (ref "Q7") (pin "1") (pinfunction "1_1") (pintype "passive"))
      (node (ref "Q9") (pin "1") (pinfunction "1_1") (pintype "passive"))
    )
    (net (code "11") (name "Net-(C9-Pad2)") (class "Default")
      (node (ref "C9") (pin "2") (pinfunction "2_2") (pintype "passive"))
      (node (ref "R9") (pin "2") (pinfunction "2_2") (pintype "passive"))
    )
    (net (code "12") (name "Net-(C10-Pad2)") (class "Default")
      (node (ref "C10") (pin "2") (pinfunction "2_2") (pintype "passive"))
      (node (ref "R2") (pin "1") (pinfunction "1_1") (pintype "passive"))
    )
    (net (code "13") (name "Net-(C11-Pad1)") (class "Default")
      (node (ref "C11") (pin "1") (pinfunction "1_1") (pintype "passive"))
      (node (ref "C7") (pin "2") (pinfunction "2_2") (pintype "passive"))
      (node (ref "D1") (pin "C") (pinfunction "C_C") (pintype "passive"))
      (node (ref "D2") (pin "A") (pinfunction "A_A") (pintype "passive"))
      (node (ref "JP2") (pin "2") (pinfunction "2_2") (pintype "passive"))
    )
    (net (code "14") (name "Net-(C13-Pad2)") (class "Default")
      (node (ref "C13") (pin "2") (pinfunction "2_2") (pintype "passive"))
      (node (ref "R15") (pin "1") (pinfunction "1_1") (pintype "passive"))
      (node (ref "R16") (pin "2") (pinfunction "2_2") (pintype "passive"))
    )
    (net (code "15") (name "Net-(C15-Pad1)") (class "Default")
      (node (ref "C15") (pin "1") (pinfunction "1_1") (pintype "passive"))
      (node (ref "JP1") (pin "2") (pinfunction "2_2") (pintype "passive"))
    )
    (net (code "16") (name "Net-(C16-Pad1)") (class "Default")
      (node (ref "C16") (pin "1") (pinfunction "1_1") (pintype "passive"))
      (node (ref "R19") (pin "1") (pinfunction "1_1") (pintype "passive"))
    )
    (net (code "17") (name "Net-(C16-Pad2)") (class "Default")
      (node (ref "C16") (pin "2") (pinfunction "2_2") (pintype "passive"))
      (node (ref "C6") (pin "2") (pinfunction "2_2") (pintype "passive"))
      (node (ref "Q7") (pin "2") (pinfunction "2_2") (pintype "passive"))
      (node (ref "Q9") (pin "2") (pinfunction "2_2") (pintype "passive"))
    )
    (net (code "18") (name "Net-(C21-Pad+)") (class "Default")
      (node (ref "C21") (pin "+") (pinfunction "+_+") (pintype "passive"))
      (node (ref "R30") (pin "2") (pinfunction "2_2") (pintype "passive"))
      (node (ref "R31") (pin "1") (pinfunction "1_1") (pintype "passive"))
    )
    (net (code "19") (name "Net-(C22-Pad1)") (class "Default")
      (node (ref "C22") (pin "1") (pinfunction "1_1") (pintype "passive"))
      (node (ref "C35") (pin "-") (pinfunction "-_-") (pintype "passive"))
      (node (ref "C41") (pin "-") (pinfunction "-_-") (pintype "passive"))
      (node (ref "JP1") (pin "4") (pinfunction "4_4") (pintype "passive"))
      (node (ref "JP1") (pin "5") (pinfunction "5_5") (pintype "passive"))
      (node (ref "R60") (pin "2") (pinfunction "2_2") (pintype "passive"))
    )
    (net (code "20") (name "Net-(C24-Pad2)") (class "Default")
      (node (ref "C24") (pin "2") (pinfunction "2_2") (pintype "passive"))
      (node (ref "Q18") (pin "S") (pinfunction "S_S") (pintype "passive"))
      (node (ref "Q19") (pin "S") (pinfunction "S_S") (pintype "passive"))
      (node (ref "R25") (pin "2") (pinfunction "2_2") (pintype "passive"))
    )
    (net (code "21") (name "Net-(C25-Pad+)") (class "Default")
      (node (ref "C25") (pin "+") (pinfunction "+_+") (pintype "passive"))
      (node (ref "IC1") (pin "OUT") (pinfunction "OUT_OUT") (pintype "passive"))
      (node (ref "R26") (pin "A") (pinfunction "A_A") (pintype "passive"))
    )
    (net (code "22") (name "Net-(C26-E)") (class "Default")
      (node (ref "C26") (pin "1") (pinfunction "E_1") (pintype "passive"))
      (node (ref "K1") (pin "1") (pinfunction "O_1") (pintype "passive"))
    )
    (net (code "23") (name "Net-(C27-E)") (class "Default")
      (node (ref "C27") (pin "1") (pinfunction "E_1") (pintype "passive"))
      (node (ref "K1") (pin "10") (pinfunction "S_10") (pintype "passive"))
    )
    (net (code "24") (name "Net-(C28-Pad-)") (class "Default")
      (node (ref "C28") (pin "-") (pinfunction "-_-") (pintype "passive"))
      (node (ref "JP7") (pin "2") (pinfunction "2_2") (pintype "passive"))
    )
    (net (code "25") (name "Net-(C29-Pad+)") (class "Default")
      (node (ref "C29") (pin "+") (pinfunction "+_+") (pintype "passive"))
      (node (ref "JP5") (pin "2") (pinfunction "2_2") (pintype "passive"))
    )
    (net (code "26") (name "Net-(C29-Pad-)") (class "Default")
      (node (ref "C29") (pin "-") (pinfunction "-_-") (pintype "passive"))
      (node (ref "R27") (pin "2") (pinfunction "2_2") (pintype "passive"))
      (node (ref "R28") (pin "1") (pinfunction "1_1") (pintype "passive"))
    )
    (net (code "27") (name "Net-(C32-Pad+)") (class "Default")
      (node (ref "C32") (pin "+") (pinfunction "+_+") (pintype "passive"))
      (node (ref "R36") (pin "1") (pinfunction "1_1") (pintype "passive"))
      (node (ref "R37") (pin "2") (pinfunction "2_2") (pintype "passive"))
    )
    (net (code "28") (name "Net-(C37-Pad-)") (class "Default")
      (node (ref "C37") (pin "-") (pinfunction "-_-") (pintype "passive"))
      (node (ref "R44") (pin "1") (pinfunction "1_1") (pintype "passive"))
    )
    (net (code "29") (name "Net-(C38-Pad-)") (class "Default")
      (node (ref "C38") (pin "-") (pinfunction "-_-") (pintype "passive"))
      (node (ref "C39") (pin "2") (pinfunction "2_2") (pintype "passive"))
      (node (ref "JP6") (pin "1") (pinfunction "1_1") (pintype "passive"))
      (node (ref "R49") (pin "2") (pinfunction "2_2") (pintype "passive"))
    )
    (net (code "30") (name "Net-(C40-Pad+)") (class "Default")
      (node (ref "C40") (pin "+") (pinfunction "+_+") (pintype "passive"))
      (node (ref "R46") (pin "1") (pinfunction "1_1") (pintype "passive"))
      (node (ref "R47") (pin "1") (pinfunction "1_1") (pintype "passive"))
      (node (ref "R48") (pin "1") (pinfunction "1_1") (pintype "passive"))
      (node (ref "R49") (pin "1") (pinfunction "1_1") (pintype "passive"))
    )
    (net (code "31") (name "Net-(C43-Pad+)") (class "Default")
      (node (ref "C43") (pin "+") (pinfunction "+_+") (pintype "passive"))
      (node (ref "R51") (pin "2") (pinfunction "2_2") (pintype "passive"))
      (node (ref "R53") (pin "1") (pinfunction "1_1") (pintype "passive"))
    )
    (net (code "32") (name "Net-(C46-Pad+)") (class "Default")
      (node (ref "C46") (pin "+") (pinfunction "+_+") (pintype "passive"))
      (node (ref "R54") (pin "1") (pinfunction "1_1") (pintype "passive"))
      (node (ref "R55") (pin "1") (pinfunction "1_1") (pintype "passive"))
    )
    (net (code "33") (name "Net-(C47-Pad1)") (class "Default")
      (node (ref "C47") (pin "1") (pinfunction "1_1") (pintype "passive"))
      (node (ref "C48") (pin "2") (pinfunction "2_2") (pintype "passive"))
      (node (ref "R57") (pin "1") (pinfunction "1_1") (pintype "passive"))
    )
    (net (code "34") (name "Net-(C48-Pad1)") (class "Default")
      (node (ref "C48") (pin "1") (pinfunction "1_1") (pintype "passive"))
      (node (ref "C49") (pin "2") (pinfunction "2_2") (pintype "passive"))
      (node (ref "R58") (pin "1") (pinfunction "1_1") (pintype "passive"))
    )
    (net (code "35") (name "Net-(C57-E)") (class "Default")
      (node (ref "C57") (pin "1") (pinfunction "E_1") (pintype "passive"))
      (node (ref "JP24") (pin "2") (pinfunction "2_2") (pintype "passive"))
    )
    (net (code "36") (name "Net-(C58-Pad1)") (class "Default")
      (node (ref "C58") (pin "1") (pinfunction "1_1") (pintype "passive"))
      (node (ref "JP15") (pin "2") (pinfunction "2_2") (pintype "passive"))
      (node (ref "JP16") (pin "1") (pinfunction "1_1") (pintype "passive"))
      (node (ref "JP24") (pin "1") (pinfunction "1_1") (pintype "passive"))
    )
    (net (code "37") (name "Net-(C59-Pad1)") (class "Default")
      (node (ref "C59") (pin "1") (pinfunction "1_1") (pintype "passive"))
      (node (ref "JP16") (pin "2") (pinfunction "2_2") (pintype "passive"))
      (node (ref "JP17") (pin "1") (pinfunction "1_1") (pintype "passive"))
      (node (ref "JP25") (pin "1") (pinfunction "1_1") (pintype "passive"))
    )
    (net (code "38") (name "Net-(C60-Pad1)") (class "Default")
      (node (ref "C60") (pin "1") (pinfunction "1_1") (pintype "passive"))
      (node (ref "JP17") (pin "2") (pinfunction "2_2") (pintype "passive"))
      (node (ref "JP18") (pin "1") (pinfunction "1_1") (pintype "passive"))
      (node (ref "JP26") (pin "1") (pinfunction "1_1") (pintype "passive"))
    )
    (net (code "39") (name "Net-(C63-Pad1)") (class "Default")
      (node (ref "C63") (pin "1") (pinfunction "1_1") (pintype "passive"))
      (node (ref "JP19") (pin "2") (pinfunction "2_2") (pintype "passive"))
      (node (ref "JP20") (pin "1") (pinfunction "1_1") (pintype "passive"))
    )
    (net (code "40") (name "Net-(C64-Pad1)") (class "Default")
      (node (ref "C64") (pin "1") (pinfunction "1_1") (pintype "passive"))
      (node (ref "JP20") (pin "2") (pinfunction "2_2") (pintype "passive"))
      (node (ref "JP21") (pin "1") (pinfunction "1_1") (pintype "passive"))
    )
    (net (code "41") (name "Net-(C65-Pad1)") (class "Default")
      (node (ref "C65") (pin "1") (pinfunction "1_1") (pintype "passive"))
      (node (ref "JP21") (pin "2") (pinfunction "2_2") (pintype "passive"))
      (node (ref "JP22") (pin "1") (pinfunction "1_1") (pintype "passive"))
    )
    (net (code "42") (name "Net-(C66-Pad1)") (class "Default")
      (node (ref "C66") (pin "1") (pinfunction "1_1") (pintype "passive"))
      (node (ref "JP22") (pin "2") (pinfunction "2_2") (pintype "passive"))
      (node (ref "JP23") (pin "1") (pinfunction "1_1") (pintype "passive"))
    )
    (net (code "43") (name "Net-(C68-E)") (class "Default")
      (node (ref "C68") (pin "1") (pinfunction "E_1") (pintype "passive"))
      (node (ref "JP25") (pin "2") (pinfunction "2_2") (pintype "passive"))
    )
    (net (code "44") (name "Net-(C69-E)") (class "Default")
      (node (ref "C69") (pin "1") (pinfunction "E_1") (pintype "passive"))
      (node (ref "JP26") (pin "2") (pinfunction "2_2") (pintype "passive"))
    )
    (net (code "45") (name "Net-(D1-PadA)") (class "Default")
      (node (ref "D1") (pin "A") (pinfunction "A_A") (pintype "passive"))
      (node (ref "JP1") (pin "6") (pinfunction "6_6") (pintype "passive"))
    )
    (net (code "46") (name "Net-(D2-PadC)") (class "Default")
      (node (ref "D2") (pin "C") (pinfunction "C_C") (pintype "passive"))
      (node (ref "JP1") (pin "3") (pinfunction "3_3") (pintype "passive"))
    )
    (net (code "47") (name "Net-(D3-PadC)") (class "Default")
      (node (ref "D3") (pin "C") (pinfunction "C_C") (pintype "passive"))
      (node (ref "D4") (pin "A") (pinfunction "A_A") (pintype "passive"))
    )
    (net (code "48") (name "Net-(JP3-Pad3)") (class "Default")
      (node (ref "JP3") (pin "3") (pinfunction "3_3") (pintype "passive"))
      (node (ref "Q18") (pin "D") (pinfunction "D_D") (pintype "passive"))
    )
    (net (code "49") (name "Net-(JP3-Pad4)") (class "Default")
      (node (ref "JP3") (pin "4") (pinfunction "4_4") (pintype "passive"))
      (node (ref "JP3") (pin "5") (pinfunction "5_5") (pintype "passive"))
      (node (ref "Q1") (pin "1") (pinfunction "1_1") (pintype "passive"))
      (node (ref "Q2") (pin "1") (pinfunction "1_1") (pintype "passive"))
    )
    (net (code "50") (name "Net-(JP3-Pad6)") (class "Default")
      (node (ref "JP3") (pin "6") (pinfunction "6_6") (pintype "passive"))
      (node (ref "Q19") (pin "D") (pinfunction "D_D") (pintype "passive"))
    )
    (net (code "51") (name "Net-(JP4-Pad2)") (class "Default")
      (node (ref "JP4") (pin "2") (pinfunction "2_2") (pintype "passive"))
      (node (ref "X1") (pin "1") (pinfunction "1_1") (pintype "passive"))
    )
    (net (code "52") (name "Net-(JP4-Pad4)") (class "Default")
      (node (ref "JP4") (pin "4") (pinfunction "4_4") (pintype "passive"))
      (node (ref "Q18") (pin "G") (pinfunction "G_G") (pintype "passive"))
    )
    (net (code "53") (name "Net-(JP4-Pad5)") (class "Default")
      (node (ref "JP4") (pin "5") (pinfunction "5_5") (pintype "passive"))
      (node (ref "Q19") (pin "G") (pinfunction "G_G") (pintype "passive"))
    )
    (net (code "54") (name "Net-(JP9-Pad1)") (class "Default")
      (node (ref "JP9") (pin "1") (pinfunction "1_1") (pintype "passive"))
      (node (ref "R52") (pin "1") (pinfunction "1_1") (pintype "passive"))
    )
    (net (code "55") (name "Net-(JP10-Pad1)") (class "Default")
      (node (ref "JP10") (pin "1") (pinfunction "1_1") (pintype "passive"))
      (node (ref "R59") (pin "2") (pinfunction "2_2") (pintype "passive"))
    )
    (net (code "56") (name "Net-(JP27-Pad1)") (class "Default")
      (node (ref "JP27") (pin "1") (pinfunction "1_1") (pintype "passive"))
      (node (ref "R64") (pin "1") (pinfunction "1_1") (pintype "passive"))
    )
    (net (code "57") (name "Net-(K1A-2)") (class "Default")
      (node (ref "C44") (pin "1") (pinfunction "1_1") (pintype "passive"))
      (node (ref "D5") (pin "A") (pinfunction "A_A") (pintype "passive"))
      (node (ref "K1") (pin "9") (pinfunction "2_9") (pintype "passive"))
      (node (ref "Q27") (pin "1") (pinfunction "C_1") (pintype "passive"))
    )
    (net (code "58") (name "Net-(K1B-P-Pad5)") (class "Default")
      (node (ref "K1") (pin "5") (pinfunction "P_5") (pintype "passive"))
      (node (ref "L1") (pin "2") (pinfunction "2_2") (pintype "passive"))
    )
    (net (code "59") (name "Net-(K2A-O)") (class "Default")
      (node (ref "C50") (pin "-") (pinfunction "-_-") (pintype "passive"))
      (node (ref "K2") (pin "6") (pinfunction "O_6") (pintype "passive"))
    )
    (net (code "60") (name "Net-(K2A-P)") (class "Default")
      (node (ref "JP7") (pin "3") (pinfunction "3_3") (pintype "passive"))
      (node (ref "K2") (pin "4") (pinfunction "P_4") (pintype "passive"))
    )
    (net (code "61") (name "Net-(K2A-S)") (class "Default")
      (node (ref "K2") (pin "8") (pinfunction "S_8") (pintype "passive"))
      (node (ref "R61") (pin "2") (pinfunction "2_2") (pintype "passive"))
    )
    (net (code "62") (name "Net-(K3A-2)") (class "Default")
      (node (ref "C70") (pin "1") (pinfunction "1_1") (pintype "passive"))
      (node (ref "C71") (pin "1") (pinfunction "1_1") (pintype "passive"))
      (node (ref "D7") (pin "A") (pinfunction "A_A") (pintype "passive"))
      (node (ref "K3") (pin "9") (pinfunction "2_9") (pintype "passive"))
      (node (ref "K4") (pin "9") (pinfunction "2_9") (pintype "passive"))
      (node (ref "Q39") (pin "1") (pinfunction "C_1") (pintype "passive"))
    )
    (net (code "63") (name "Net-(K3B-O)") (class "Default")
      (node (ref "C62") (pin "1") (pinfunction "1_1") (pintype "passive"))
      (node (ref "JP19") (pin "1") (pinfunction "1_1") (pintype "passive"))
      (node (ref "K3") (pin "1") (pinfunction "O_1") (pintype "passive"))
    )
    (net (code "64") (name "Net-(K3B-S)") (class "Default")
      (node (ref "C56") (pin "1") (pinfunction "1_1") (pintype "passive"))
      (node (ref "JP15") (pin "1") (pinfunction "1_1") (pintype "passive"))
      (node (ref "K3") (pin "10") (pinfunction "S_10") (pintype "passive"))
    )
    (net (code "65") (name "Net-(K4B-O)") (class "Default")
      (node (ref "C67") (pin "1") (pinfunction "1_1") (pintype "passive"))
      (node (ref "JP23") (pin "2") (pinfunction "2_2") (pintype "passive"))
      (node (ref "K4") (pin "1") (pinfunction "O_1") (pintype "passive"))
    )
    (net (code "66") (name "Net-(K4B-P-Pad6)") (class "Default")
      (node (ref "K4") (pin "6") (pinfunction "P_6") (pintype "passive"))
      (node (ref "X3") (pin "1") (pinfunction "1_1") (pintype "passive"))
    )
    (net (code "67") (name "Net-(K4B-S)") (class "Default")
      (node (ref "C61") (pin "1") (pinfunction "1_1") (pintype "passive"))
      (node (ref "JP18") (pin "2") (pinfunction "2_2") (pintype "passive"))
      (node (ref "K4") (pin "10") (pinfunction "S_10") (pintype "passive"))
    )
    (net (code "68") (name "Net-(L1-Pad1)") (class "Default")
      (node (ref "L1") (pin "1") (pinfunction "1_1") (pintype "passive"))
      (node (ref "Q17") (pin "1") (pinfunction "1_1") (pintype "passive"))
    )
    (net (code "69") (name "Net-(Q8-B)") (class "Default")
      (node (ref "C7") (pin "1") (pinfunction "1_1") (pintype "passive"))
      (node (ref "C9") (pin "1") (pinfunction "1_1") (pintype "passive"))
      (node (ref "Q8") (pin "2") (pinfunction "B_2") (pintype "passive"))
      (node (ref "R6") (pin "1") (pinfunction "1_1") (pintype "passive"))
      (node (ref "R8") (pin "1") (pinfunction "1_1") (pintype "passive"))
    )
    (net (code "70") (name "Net-(Q8-E)") (class "Default")
      (node (ref "C10") (pin "1") (pinfunction "1_1") (pintype "passive"))
      (node (ref "Q8") (pin "3") (pinfunction "E_3") (pintype "passive"))
      (node (ref "R4") (pin "1") (pinfunction "1_1") (pintype "passive"))
    )
    (net (code "71") (name "Net-(Q10-B)") (class "Default")
      (node (ref "Q10") (pin "2") (pinfunction "B_2") (pintype "passive"))
      (node (ref "Q8") (pin "1") (pinfunction "C_1") (pintype "passive"))
      (node (ref "R5") (pin "1") (pinfunction "1_1") (pintype "passive"))
      (node (ref "R9") (pin "1") (pinfunction "1_1") (pintype "passive"))
    )
    (net (code "72") (name "Net-(Q10-C)") (class "Default")
      (node (ref "C8") (pin "1") (pinfunction "1_1") (pintype "passive"))
      (node (ref "Q10") (pin "1") (pinfunction "C_1") (pintype "passive"))
      (node (ref "Q11") (pin "1") (pinfunction "C_1") (pintype "passive"))
      (node (ref "R5") (pin "2") (pinfunction "2_2") (pintype "passive"))
      (node (ref "R7") (pin "2") (pinfunction "2_2") (pintype "passive"))
      (node (ref "R8") (pin "2") (pinfunction "2_2") (pintype "passive"))
    )
    (net (code "73") (name "Net-(Q10-E)") (class "Default")
      (node (ref "Q10") (pin "3") (pinfunction "E_3") (pintype "passive"))
      (node (ref "Q11") (pin "2") (pinfunction "B_2") (pintype "passive"))
      (node (ref "R3") (pin "1") (pinfunction "1_1") (pintype "passive"))
    )
    (net (code "74") (name "Net-(Q11-E)") (class "Default")
      (node (ref "Q11") (pin "3") (pinfunction "E_3") (pintype "passive"))
      (node (ref "R1") (pin "1") (pinfunction "1_1") (pintype "passive"))
      (node (ref "R19") (pin "2") (pinfunction "2_2") (pintype "passive"))
    )
    (net (code "75") (name "Net-(Q12-B)") (class "Default")
      (node (ref "Q12") (pin "2") (pinfunction "B_2") (pintype "passive"))
      (node (ref "Q13") (pin "3") (pinfunction "E_3") (pintype "passive"))
      (node (ref "R11") (pin "1") (pinfunction "1_1") (pintype "passive"))
    )
    (net (code "76") (name "Net-(Q12-C)") (class "Default")
      (node (ref "C14") (pin "2") (pinfunction "2_2") (pintype "passive"))
      (node (ref "Q12") (pin "1") (pinfunction "C_1") (pintype "passive"))
      (node (ref "Q13") (pin "1") (pinfunction "C_1") (pintype "passive"))
      (node (ref "R14") (pin "1") (pinfunction "1_1") (pintype "passive"))
      (node (ref "R16") (pin "1") (pinfunction "1_1") (pintype "passive"))
      (node (ref "R17") (pin "1") (pinfunction "1_1") (pintype "passive"))
    )
    (net (code "77") (name "Net-(Q12-E)") (class "Default")
      (node (ref "C11") (pin "2") (pinfunction "2_2") (pintype "passive"))
      (node (ref "Q12") (pin "3") (pinfunction "E_3") (pintype "passive"))
      (node (ref "R12") (pin "1") (pinfunction "1_1") (pintype "passive"))
    )
    (net (code "78") (name "Net-(Q13-B)") (class "Default")
      (node (ref "Q13") (pin "2") (pinfunction "B_2") (pintype "passive"))
      (node (ref "Q14") (pin "1") (pinfunction "C_1") (pintype "passive"))
      (node (ref "R15") (pin "2") (pinfunction "2_2") (pintype "passive"))
    )
    (net (code "79") (name "Net-(Q14-B)") (class "Default")
      (node (ref "C12") (pin "2") (pinfunction "2_2") (pintype "passive"))
      (node (ref "Q14") (pin "2") (pinfunction "B_2") (pintype "passive"))
      (node (ref "R13") (pin "1") (pinfunction "1_1") (pintype "passive"))
      (node (ref "R14") (pin "2") (pinfunction "2_2") (pintype "passive"))
    )
    (net (code "80") (name "Net-(Q14-E)") (class "Default")
      (node (ref "C6") (pin "1") (pinfunction "1_1") (pintype "passive"))
      (node (ref "Q14") (pin "3") (pinfunction "E_3") (pintype "passive"))
      (node (ref "R10") (pin "1") (pinfunction "1_1") (pintype "passive"))
    )
    (net (code "81") (name "Net-(Q15-B)") (class "Default")
      (node (ref "Q15") (pin "2") (pinfunction "B_2") (pintype "passive"))
      (node (ref "R20") (pin "2") (pinfunction "2_2") (pintype "passive"))
    )
    (net (code "82") (name "Net-(Q15-C)") (class "Default")
      (node (ref "C19") (pin "1") (pinfunction "1_1") (pintype "passive"))
      (node (ref "Q15") (pin "1") (pinfunction "C_1") (pintype "passive"))
      (node (ref "Q16") (pin "1") (pinfunction "C_1") (pintype "passive"))
      (node (ref "R23") (pin "1") (pinfunction "1_1") (pintype "passive"))
      (node (ref "R24") (pin "1") (pinfunction "1_1") (pintype "passive"))
    )
    (net (code "83") (name "Net-(Q15-E)") (class "Default")
      (node (ref "C15") (pin "2") (pinfunction "2_2") (pintype "passive"))
      (node (ref "Q15") (pin "3") (pinfunction "E_3") (pintype "passive"))
      (node (ref "R18") (pin "1") (pinfunction "1_1") (pintype "passive"))
    )
    (net (code "84") (name "Net-(Q16-B)") (class "Default")
      (node (ref "C18") (pin "1") (pinfunction "1_1") (pintype "passive"))
      (node (ref "Q16") (pin "2") (pinfunction "B_2") (pintype "passive"))
      (node (ref "Q17") (pin "2") (pinfunction "2_2") (pintype "passive"))
      (node (ref "R22") (pin "1") (pinfunction "1_1") (pintype "passive"))
      (node (ref "R23") (pin "2") (pinfunction "2_2") (pintype "passive"))
    )
    (net (code "85") (name "Net-(Q16-E)") (class "Default")
      (node (ref "C17") (pin "1") (pinfunction "1_1") (pintype "passive"))
      (node (ref "C18") (pin "2") (pinfunction "2_2") (pintype "passive"))
      (node (ref "Q16") (pin "3") (pinfunction "E_3") (pintype "passive"))
      (node (ref "R20") (pin "1") (pinfunction "1_1") (pintype "passive"))
      (node (ref "R21") (pin "1") (pinfunction "1_1") (pintype "passive"))
    )
    (net (code "86") (name "Net-(Q20-B)") (class "Default")
      (node (ref "C20") (pin "+") (pinfunction "+_+") (pintype "passive"))
      (node (ref "D3") (pin "A") (pinfunction "A_A") (pintype "passive"))
      (node (ref "Q20") (pin "2") (pinfunction "B_2") (pintype "passive"))
      (node (ref "R29") (pin "2") (pinfunction "2_2") (pintype "passive"))
    )
    (net (code "87") (name "Net-(Q20-C)") (class "Default")
      (node (ref "C30") (pin "+") (pinfunction "+_+") (pintype "passive"))
      (node (ref "Q20") (pin "1") (pinfunction "C_1") (pintype "passive"))
      (node (ref "R29") (pin "1") (pinfunction "1_1") (pintype "passive"))
      (node (ref "R32") (pin "1") (pinfunction "1_1") (pintype "passive"))
      (node (ref "R34") (pin "2") (pinfunction "2_2") (pintype "passive"))
    )
    (net (code "88") (name "Net-(Q20-E)") (class "Default")
      (node (ref "Q20") (pin "3") (pinfunction "E_3") (pintype "passive"))
      (node (ref "R27") (pin "1") (pinfunction "1_1") (pintype "passive"))
    )
    (net (code "89") (name "Net-(Q21-B)") (class "Default")
      (node (ref "C20") (pin "-") (pinfunction "-_-") (pintype "passive"))
      (node (ref "D4") (pin "C") (pinfunction "C_C") (pintype "passive"))
      (node (ref "Q21") (pin "2") (pinfunction "B_2") (pintype "passive"))
      (node (ref "Q22") (pin "1") (pinfunction "C_1") (pintype "passive"))
    )
    (net (code "90") (name "Net-(Q21-E)") (class "Default")
      (node (ref "Q21") (pin "3") (pinfunction "E_3") (pintype "passive"))
      (node (ref "R28") (pin "2") (pinfunction "2_2") (pintype "passive"))
    )
    (net (code "91") (name "Net-(Q22-B)") (class "Default")
      (node (ref "C28") (pin "+") (pinfunction "+_+") (pintype "passive"))
      (node (ref "Q22") (pin "2") (pinfunction "B_2") (pintype "passive"))
      (node (ref "R32") (pin "2") (pinfunction "2_2") (pintype "passive"))
      (node (ref "R33") (pin "1") (pinfunction "1_1") (pintype "passive"))
    )
    (net (code "92") (name "Net-(Q22-E)") (class "Default")
      (node (ref "Q22") (pin "3") (pinfunction "E_3") (pintype "passive"))
      (node (ref "R30") (pin "1") (pinfunction "1_1") (pintype "passive"))
    )
    (net (code "93") (name "Net-(Q23-B)") (class "Default")
      (node (ref "C31") (pin "+") (pinfunction "+_+") (pintype "passive"))
      (node (ref "Q23") (pin "2") (pinfunction "B_2") (pintype "passive"))
      (node (ref "R35") (pin "1") (pinfunction "1_1") (pintype "passive"))
    )
    (net (code "94") (name "Net-(Q23-E)") (class "Default")
      (node (ref "Q23") (pin "3") (pinfunction "E_3") (pintype "passive"))
      (node (ref "R36") (pin "2") (pinfunction "2_2") (pintype "passive"))
      (node (ref "R39") (pin "2") (pinfunction "2_2") (pintype "passive"))
      (node (ref "R41") (pin "2") (pinfunction "2_2") (pintype "passive"))
    )
    (net (code "95") (name "Net-(Q24-B)") (class "Default")
      (node (ref "Q24") (pin "2") (pinfunction "B_2") (pintype "passive"))
      (node (ref "Q25") (pin "1") (pinfunction "C_1") (pintype "passive"))
      (node (ref "R39") (pin "1") (pinfunction "1_1") (pintype "passive"))
    )
    (net (code "96") (name "Net-(Q24-C)") (class "Default")
      (node (ref "C50") (pin "+") (pinfunction "+_+") (pintype "passive"))
      (node (ref "Q24") (pin "1") (pinfunction "C_1") (pintype "passive"))
      (node (ref "R37") (pin "1") (pinfunction "1_1") (pintype "passive"))
    )
    (net (code "97") (name "Net-(Q24-E)") (class "Default")
      (node (ref "C33") (pin "+") (pinfunction "+_+") (pintype "passive"))
      (node (ref "Q24") (pin "3") (pinfunction "E_3") (pintype "passive"))
      (node (ref "R38") (pin "2") (pinfunction "2_2") (pintype "passive"))
    )
    (net (code "98") (name "Net-(Q25-B)") (class "Default")
      (node (ref "C36") (pin "+") (pinfunction "+_+") (pintype "passive"))
      (node (ref "Q25") (pin "2") (pinfunction "B_2") (pintype "passive"))
      (node (ref "R41") (pin "1") (pinfunction "1_1") (pintype "passive"))
      (node (ref "R42") (pin "1") (pinfunction "1_1") (pintype "passive"))
    )
    (net (code "99") (name "Net-(Q25-E)") (class "Default")
      (node (ref "C35") (pin "+") (pinfunction "+_+") (pintype "passive"))
      (node (ref "Q25") (pin "3") (pinfunction "E_3") (pintype "passive"))
      (node (ref "R40") (pin "2") (pinfunction "2_2") (pintype "passive"))
    )
    (net (code "100") (name "Net-(Q26-B)") (class "Default")
      (node (ref "C38") (pin "+") (pinfunction "+_+") (pintype "passive"))
      (node (ref "Q26") (pin "2") (pinfunction "B_2") (pintype "passive"))
      (node (ref "R45") (pin "1") (pinfunction "1_1") (pintype "passive"))
      (node (ref "R46") (pin "2") (pinfunction "2_2") (pintype "passive"))
    )
    (net (code "101") (name "Net-(Q26-C)") (class "Default")
      (node (ref "C41") (pin "+") (pinfunction "+_+") (pintype "passive"))
      (node (ref "Q26") (pin "1") (pinfunction "C_1") (pintype "passive"))
      (node (ref "R47") (pin "2") (pinfunction "2_2") (pintype "passive"))
    )
    (net (code "102") (name "Net-(Q26-E)") (class "Default")
      (node (ref "C37") (pin "+") (pinfunction "+_+") (pintype "passive"))
      (node (ref "Q26") (pin "3") (pinfunction "E_3") (pintype "passive"))
      (node (ref "R43") (pin "1") (pinfunction "1_1") (pintype "passive"))
    )
    (net (code "103") (name "Net-(Q27-B)") (class "Default")
      (node (ref "Q27") (pin "2") (pinfunction "B_2") (pintype "passive"))
      (node (ref "R52") (pin "2") (pinfunction "2_2") (pintype "passive"))
    )
    (net (code "104") (name "Net-(Q28-B)") (class "Default")
      (node (ref "JP8") (pin "1") (pinfunction "1_1") (pintype "passive"))
      (node (ref "Q28") (pin "2") (pinfunction "B_2") (pintype "passive"))
    )
    (net (code "105") (name "Net-(Q28-C)") (class "Default")
      (node (ref "Q28") (pin "1") (pinfunction "C_1") (pintype "passive"))
      (node (ref "Q29") (pin "2") (pinfunction "B_2") (pintype "passive"))
      (node (ref "R50") (pin "2") (pinfunction "2_2") (pintype "passive"))
    )
    (net (code "106") (name "Net-(Q29-C)") (class "Default")
      (node (ref "C23") (pin "1") (pinfunction "1_1") (pintype "passive"))
      (node (ref "D6") (pin "A") (pinfunction "A_A") (pintype "passive"))
      (node (ref "K2") (pin "1") (pinfunction "1_1") (pintype "passive"))
      (node (ref "Q29") (pin "1") (pinfunction "C_1") (pintype "passive"))
    )
    (net (code "107") (name "Net-(Q30-B)") (class "Default")
      (node (ref "C47") (pin "2") (pinfunction "2_2") (pintype "passive"))
      (node (ref "Q30") (pin "2") (pinfunction "B_2") (pintype "passive"))
      (node (ref "R56") (pin "1") (pinfunction "1_1") (pintype "passive"))
      (node (ref "R59") (pin "1") (pinfunction "1_1") (pintype "passive"))
    )
    (net (code "108") (name "Net-(Q30-C)") (class "Default")
      (node (ref "C49") (pin "1") (pinfunction "1_1") (pintype "passive"))
      (node (ref "Q30") (pin "1") (pinfunction "C_1") (pintype "passive"))
      (node (ref "R54") (pin "2") (pinfunction "2_2") (pintype "passive"))
    )
    (net (code "109") (name "Net-(Q30-E)") (class "Default")
      (node (ref "Q30") (pin "3") (pinfunction "E_3") (pintype "passive"))
      (node (ref "R51") (pin "1") (pinfunction "1_1") (pintype "passive"))
      (node (ref "R60") (pin "1") (pinfunction "1_1") (pintype "passive"))
      (node (ref "R61") (pin "1") (pinfunction "1_1") (pintype "passive"))
    )
    (net (code "110") (name "Net-(Q39-B)") (class "Default")
      (node (ref "Q39") (pin "2") (pinfunction "B_2") (pintype "passive"))
      (node (ref "R64") (pin "2") (pinfunction "2_2") (pintype "passive"))
    )
    (net (code "111") (name "Net-(R25-Pad1)") (class "Default")
      (node (ref "R25") (pin "1") (pinfunction "1_1") (pintype "passive"))
      (node (ref "R26") (pin "S") (pinfunction "S_S") (pintype "passive"))
    )
    (net (code "112") (name "unconnected-(H1-MOUNT-PadB3,0)") (class "Default")
      (node (ref "H1") (pin "B3,0") (pinfunction "MOUNT_B3,0") (pintype "passive"))
    )
    (net (code "113") (name "unconnected-(H2-MOUNT-PadB3,0)") (class "Default")
      (node (ref "H2") (pin "B3,0") (pinfunction "MOUNT_B3,0") (pintype "passive"))
    )
    (net (code "114") (name "unconnected-(H3-MOUNT-PadB3,0)") (class "Default")
      (node (ref "H3") (pin "B3,0") (pinfunction "MOUNT_B3,0") (pintype "passive"))
    )
    (net (code "115") (name "unconnected-(H4-MOUNT-PadB3,0)") (class "Default")
      (node (ref "H4") (pin "B3,0") (pinfunction "MOUNT_B3,0") (pintype "passive"))
    )
    (net (code "116") (name "unconnected-(K1B-P-Pad6)") (class "Default")
      (node (ref "K1") (pin "6") (pinfunction "P_6") (pintype "passive"))
    )
    (net (code "117") (name "unconnected-(K3B-P-Pad6)") (class "Default")
      (node (ref "K3") (pin "6") (pinfunction "P_6") (pintype "passive"))
    )
    (net (code "118") (name "unconnected-(K4B-P-Pad5)") (class "Default")
      (node (ref "K4") (pin "5") (pinfunction "P_5") (pintype "passive"))
    )
  )
)
